# UC2010.net
KiCad netlist of a schematic drawn in Altium Designer
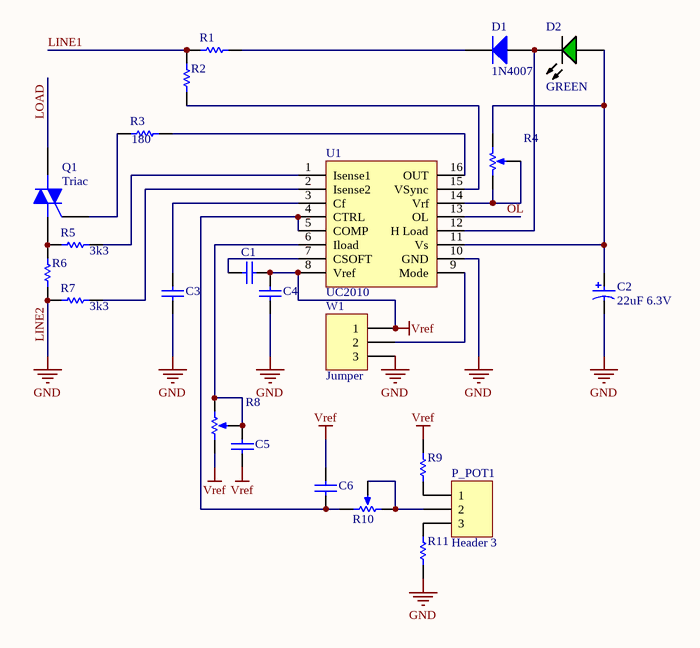
[diagram p0: UC2010.SchDoc]

(export (version "E")
  (design (tool "Eeschema 10.0.6"))
  (components
    (comp (ref "C1")
      (value "100nF 100V")
      (footprint "RC_0603")
      (description "CAPACITOR CHIP")
      (fields (field (name "MANUFACTURER") "AVX Corporation"))
      (libsource (lib "RozumLibrary") (part "CAP-0805-104-100V"))
    )
    (comp (ref "C2")
      (value "22uF 6.3V")
      (footprint "RR_CAP-B")
      (description "CAPACITOR TANTAL CASE B")
      (fields (field (name "MANUFACTURER") "AVX Corporation"))
      (libsource (lib "RozumLibrary") (part "CAP-TANT-B-226-6.3V"))
    )
    (comp (ref "C3")
      (value "100nF 100V")
      (footprint "RC_0805_T1.1")
      (description "CAPACITOR CHIP")
      (fields (field (name "MANUFACTURER") "AVX Corporation"))
      (libsource (lib "RozumLibrary") (part "CAP-0805-104-100V"))
    )
    (comp (ref "C4")
      (value "100nF 100V")
      (footprint "RC_1206_T0.95")
      (description "CAPACITOR CHIP")
      (fields (field (name "MANUFACTURER") "AVX Corporation"))
      (libsource (lib "RozumLibrary") (part "CAP-0805-104-100V"))
    )
    (comp (ref "C5")
      (value "100nF 100V")
      (footprint "RC_0805_T1.1")
      (description "CAPACITOR CHIP")
      (fields (field (name "MANUFACTURER") "AVX Corporation"))
      (libsource (lib "RozumLibrary") (part "CAP-0805-104-100V"))
    )
    (comp (ref "C6")
      (value "100nF 100V")
      (footprint "RC_0805_T1.1")
      (description "CAPACITOR CHIP")
      (fields (field (name "MANUFACTURER") "AVX Corporation"))
      (libsource (lib "RozumLibrary") (part "CAP-0805-104-100V"))
    )
    (comp (ref "D1")
      (value "1N4007")
      (footprint "RR_DO-41")
      (description "DIODE GENERAL 1000V 1A")
      (fields (field (name "MANUFACTURER") "ON Semiconductor"))
      (libsource (lib "RozumLibrary") (part "1N4007"))
    )
    (comp (ref "D2")
      (value "GREEN")
      (footprint "RR_LED-0603-GREEN")
      (description "DIODE LED 0603 GREEN")
      (fields (field (name "MANUFACTURER") "Wurth Electronics Inc."))
      (libsource (lib "RozumLibrary") (part "LED-0603-GREEN"))
    )
    (comp (ref "P_POT1")
      (value "Header 3")
      (footprint "R_POT_16K1")
      (description "Header, 3-Pin")
      (fields (field (name "PUBLISHER") "Altium Limited"))
      (libsource (lib "") (part "Header 3_1"))
    )
    (comp (ref "Q1")
      (value "Triac")
      (footprint "RR_D2PAK")
      (description "Silicon Bidirectional Triode Thyristor")
      (fields (field (name "PUBLISHER") "Altium Limited"))
      (libsource (lib "Miscellaneous Devices") (part "Triac"))
    )
    (comp (ref "R1")
      (value "Res1")
      (footprint "AXIAL-0.7")
      (description "Resistor")
      (fields (field (name "PUBLISHER") "Altium Limited"))
      (libsource (lib "Miscellaneous Devices") (part "Res1"))
    )
    (comp (ref "R2")
      (value "20k 0.1%")
      (footprint "RR_1206")
      (description "RESISTOR")
      (fields (field (name "MANUFACTURER") "Susumu"))
      (libsource (lib "RozumLibrary") (part "RES-1206-20K-0.1%"))
    )
    (comp (ref "R3")
      (value "180")
      (footprint "RR_1206")
      (description "RESISTOR")
      (fields (field (name "MANUFACTURER") "Susumu"))
      (libsource (lib "RozumLibrary") (part "RES-1206-20K-0.1%"))
    )
    (comp (ref "R4")
      (value "RPot")
      (footprint "VR5")
      (description "Potentiometer")
      (fields (field (name "PUBLISHER") "Altium Limited"))
      (libsource (lib "Schlib1") (part "RPot"))
    )
    (comp (ref "R5")
      (value "3k3")
      (footprint "RR_0805")
      (description "RESISTOR")
      (fields (field (name "MANUFACTURER") "Susumu"))
      (libsource (lib "RozumLibrary") (part "RES-1206-20K-0.1%"))
    )
    (comp (ref "R6")
      (value "Res1")
      (footprint "AXIAL-0.7")
      (description "Resistor")
      (fields (field (name "PUBLISHER") "Altium Limited"))
      (libsource (lib "Miscellaneous Devices") (part "Res1"))
    )
    (comp (ref "R7")
      (value "3k3")
      (footprint "RR_0805")
      (description "RESISTOR")
      (fields (field (name "MANUFACTURER") "Susumu"))
      (libsource (lib "RozumLibrary") (part "RES-1206-20K-0.1%"))
    )
    (comp (ref "R8")
      (value "RPot")
      (footprint "VR5")
      (description "Potentiometer")
      (fields (field (name "PUBLISHER") "Altium Limited"))
      (libsource (lib "Schlib1") (part "RPot"))
    )
    (comp (ref "R9")
      (value "3k3")
      (footprint "RR_1206")
      (description "RESISTOR")
      (fields (field (name "MANUFACTURER") "Susumu"))
      (libsource (lib "RozumLibrary") (part "RES-1206-20K-0.1%"))
    )
    (comp (ref "R10")
      (value "RPot")
      (footprint "VR5")
      (description "Potentiometer")
      (fields (field (name "PUBLISHER") "Altium Limited"))
      (libsource (lib "Schlib1") (part "RPot"))
    )
    (comp (ref "R11")
      (value "3k3")
      (footprint "RR_1206")
      (description "RESISTOR")
      (fields (field (name "MANUFACTURER") "Susumu"))
      (libsource (lib "RozumLibrary") (part "RES-1206-20K-0.1%"))
    )
    (comp (ref "U1") (value "UC2010") (footprint "RR_SO16") (libsource (lib "Schlib1") (part "UC2010")))
    (comp (ref "W1")
      (value "Jumper")
      (footprint "JUMPER-2pos")
      (description "Header, 3-Pin")
      (libsource (lib "Miscellaneous Connectors") (part "Header 3"))
    )
  )
  (nets
    (net (code "1") (name "/LINE1") (class "Default")
      (node (ref "R1") (pin "2") (pinfunction "2_2") (pintype "passive"))
      (node (ref "R2") (pin "2") (pinfunction "2_2") (pintype "passive"))
    )
    (net (code "2") (name "/LOAD") (class "Default")
      (node (ref "Q1") (pin "2") (pinfunction "M2_2") (pintype "passive"))
    )
    (net (code "3") (name "/OL") (class "Default")
      (node (ref "U1") (pin "13") (pinfunction "OL_13") (pintype "passive"))
    )
    (net (code "4") (name "GND") (class "Default")
      (node (ref "C2") (pin "2") (pinfunction "2_2") (pintype "passive"))
      (node (ref "C3") (pin "1") (pinfunction "1_1") (pintype "passive"))
      (node (ref "C4") (pin "1") (pinfunction "1_1") (pintype "passive"))
      (node (ref "R11") (pin "2") (pinfunction "2_2") (pintype "passive"))
      (node (ref "R6") (pin "2") (pinfunction "2_2") (pintype "passive"))
      (node (ref "R7") (pin "2") (pinfunction "2_2") (pintype "passive"))
      (node (ref "U1") (pin "10") (pinfunction "GND_10") (pintype "passive"))
      (node (ref "W1") (pin "3") (pinfunction "3_3") (pintype "passive"))
    )
    (net (code "5") (name "Net-(D1-A)") (class "Default")
      (node (ref "D1") (pin "1") (pinfunction "A_1") (pintype "passive"))
      (node (ref "D2") (pin "2") (pinfunction "K_2") (pintype "passive"))
      (node (ref "U1") (pin "12") (pinfunction "H_Load_12") (pintype "passive"))
    )
    (net (code "6") (name "Net-(D1-K)") (class "Default")
      (node (ref "D1") (pin "2") (pinfunction "K_2") (pintype "passive"))
      (node (ref "R1") (pin "1") (pinfunction "1_1") (pintype "passive"))
    )
    (net (code "7") (name "Net-(D2-A)") (class "Default")
      (node (ref "C2") (pin "1") (pinfunction "1_1") (pintype "passive"))
      (node (ref "D2") (pin "1") (pinfunction "A_1") (pintype "passive"))
      (node (ref "R4") (pin "3") (pinfunction "TOP_3") (pintype "passive"))
      (node (ref "U1") (pin "11") (pinfunction "Vs_11") (pintype "passive"))
    )
    (net (code "8") (name "Net-(P_POT1-Pad1)") (class "Default")
      (node (ref "P_POT1") (pin "1") (pinfunction "1_1") (pintype "passive"))
      (node (ref "R9") (pin "2") (pinfunction "2_2") (pintype "passive"))
    )
    (net (code "9") (name "Net-(P_POT1-Pad3)") (class "Default")
      (node (ref "P_POT1") (pin "3") (pinfunction "3_3") (pintype "passive"))
      (node (ref "R11") (pin "1") (pinfunction "1_1") (pintype "passive"))
    )
    (net (code "10") (name "Net-(Q1-G)") (class "Default")
      (node (ref "Q1") (pin "3") (pinfunction "G_3") (pintype "passive"))
      (node (ref "R3") (pin "2") (pinfunction "2_2") (pintype "passive"))
    )
    (net (code "11") (name "Net-(Q1-M1)") (class "Default")
      (node (ref "Q1") (pin "1") (pinfunction "M1_1") (pintype "passive"))
      (node (ref "R5") (pin "1") (pinfunction "1_1") (pintype "passive"))
      (node (ref "R6") (pin "1") (pinfunction "1_1") (pintype "passive"))
    )
    (net (code "12") (name "Net-(R4-BOT)") (class "Default")
      (node (ref "R4") (pin "1") (pinfunction "BOT_1") (pintype "passive"))
      (node (ref "R4") (pin "2") (pinfunction "TAP_2") (pintype "passive"))
      (node (ref "U1") (pin "14") (pinfunction "Vrf_14") (pintype "passive"))
    )
    (net (code "13") (name "Net-(R8-BOT)") (class "Default")
      (node (ref "C5") (pin "2") (pinfunction "2_2") (pintype "passive"))
      (node (ref "R8") (pin "1") (pinfunction "BOT_1") (pintype "passive"))
      (node (ref "R8") (pin "2") (pinfunction "TAP_2") (pintype "passive"))
      (node (ref "U1") (pin "6") (pinfunction "Iload_6") (pintype "passive"))
    )
    (net (code "14") (name "Net-(R10-BOT)") (class "Default")
      (node (ref "C6") (pin "1") (pinfunction "1_1") (pintype "passive"))
      (node (ref "R10") (pin "1") (pinfunction "BOT_1") (pintype "passive"))
      (node (ref "U1") (pin "4") (pinfunction "CTRL_4") (pintype "passive"))
      (node (ref "U1") (pin "5") (pinfunction "COMP_5") (pintype "passive"))
    )
    (net (code "15") (name "Net-(R10-TAP)") (class "Default")
      (node (ref "P_POT1") (pin "2") (pinfunction "2_2") (pintype "passive"))
      (node (ref "R10") (pin "2") (pinfunction "TAP_2") (pintype "passive"))
      (node (ref "R10") (pin "3") (pinfunction "TOP_3") (pintype "passive"))
    )
    (net (code "16") (name "Net-(U1-CSOFT)") (class "Default")
      (node (ref "C1") (pin "2") (pinfunction "2_2") (pintype "passive"))
      (node (ref "U1") (pin "7") (pinfunction "CSOFT_7") (pintype "passive"))
    )
    (net (code "17") (name "Net-(U1-Cf)") (class "Default")
      (node (ref "C3") (pin "2") (pinfunction "2_2") (pintype "passive"))
      (node (ref "U1") (pin "3") (pinfunction "Cf_3") (pintype "passive"))
    )
    (net (code "18") (name "Net-(U1-Isense1)") (class "Default")
      (node (ref "R5") (pin "2") (pinfunction "2_2") (pintype "passive"))
      (node (ref "U1") (pin "1") (pinfunction "Isense1_1") (pintype "passive"))
    )
    (net (code "19") (name "Net-(U1-Isense2)") (class "Default")
      (node (ref "R7") (pin "1") (pinfunction "1_1") (pintype "passive"))
      (node (ref "U1") (pin "2") (pinfunction "Isense2_2") (pintype "passive"))
    )
    (net (code "20") (name "Net-(U1-Mode)") (class "Default")
      (node (ref "U1") (pin "9") (pinfunction "Mode_9") (pintype "passive"))
      (node (ref "W1") (pin "2") (pinfunction "2_2") (pintype "passive"))
    )
    (net (code "21") (name "Net-(U1-OUT)") (class "Default")
      (node (ref "R3") (pin "1") (pinfunction "1_1") (pintype "passive"))
      (node (ref "U1") (pin "16") (pinfunction "OUT_16") (pintype "passive"))
    )
    (net (code "22") (name "Net-(U1-VSync)") (class "Default")
      (node (ref "R2") (pin "1") (pinfunction "1_1") (pintype "passive"))
      (node (ref "U1") (pin "15") (pinfunction "VSync_15") (pintype "passive"))
    )
    (net (code "23") (name "Vref") (class "Default")
      (node (ref "C1") (pin "1") (pinfunction "1_1") (pintype "passive"))
      (node (ref "C4") (pin "2") (pinfunction "2_2") (pintype "passive"))
      (node (ref "C5") (pin "1") (pinfunction "1_1") (pintype "passive"))
      (node (ref "C6") (pin "2") (pinfunction "2_2") (pintype "passive"))
      (node (ref "R8") (pin "3") (pinfunction "TOP_3") (pintype "passive"))
      (node (ref "R9") (pin "1") (pinfunction "1_1") (pintype "passive"))
      (node (ref "U1") (pin "8") (pinfunction "Vref_8") (pintype "passive"))
      (node (ref "W1") (pin "1") (pinfunction "1_1") (pintype "passive"))
    )
  )
)
